# Power.net
KiCad netlist of a schematic drawn in Altium Designer
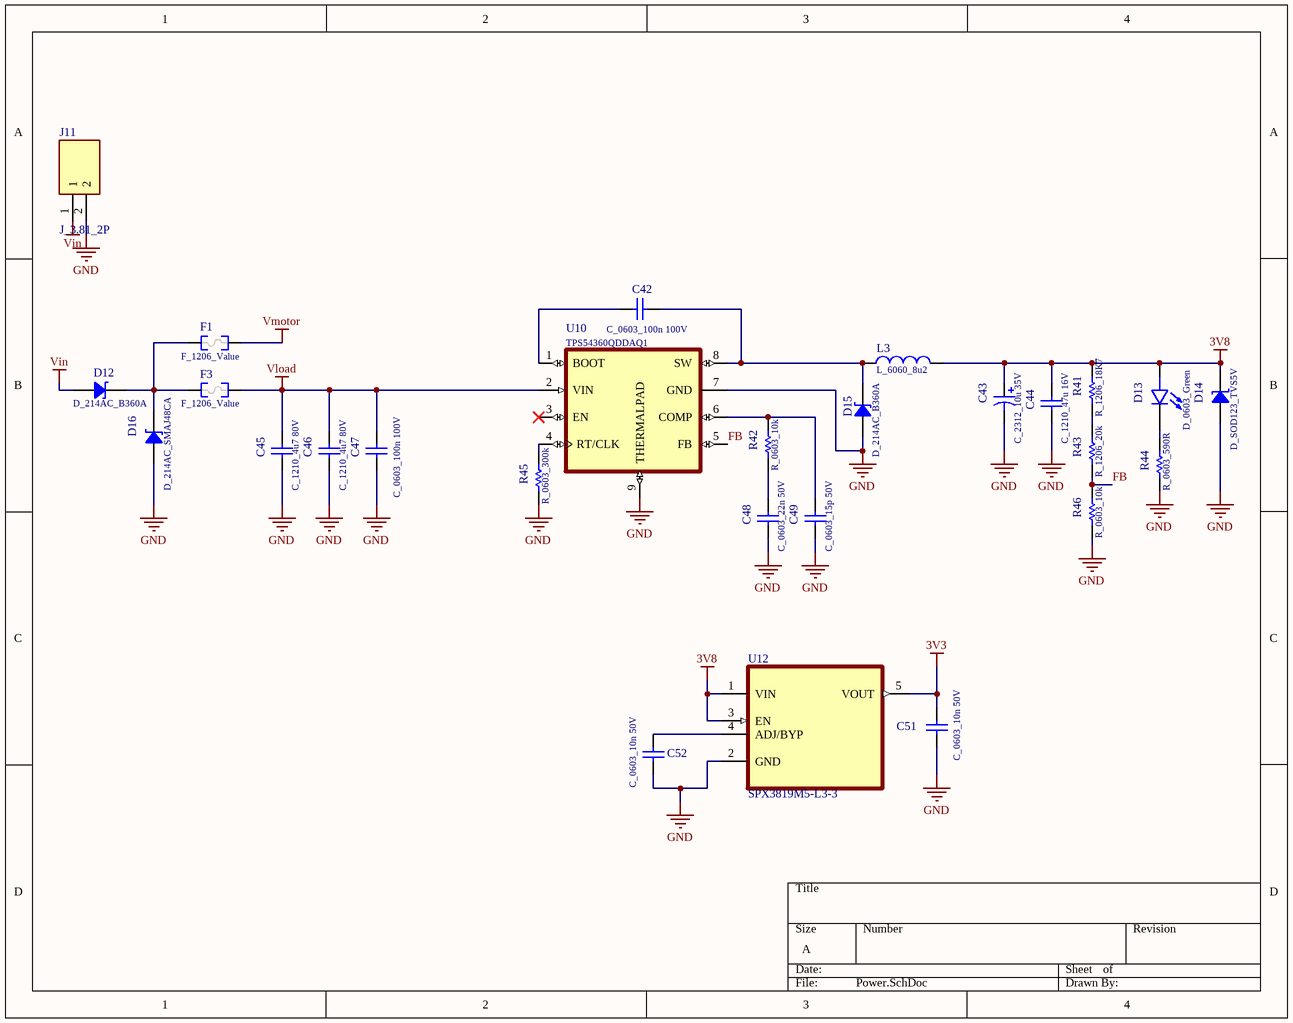
[diagram p0: Power.SchDoc]

(export (version "E")
  (design (tool "Eeschema 10.0.6"))
  (components
    (comp (ref "C42")
      (value "C_0603_100n 100V")
      (footprint "CAP 0603")
      (description "Capacitor")
      (fields (field (name "PUBLISHER") "Altium Limited"))
      (libsource (lib "HUE") (part "Cap"))
    )
    (comp (ref "C43")
      (value "C_2312_10u 35V")
      (footprint "CAP 2312 TAN")
      (description "Capacitor Tantalium")
      (fields (field (name "PUBLISHER") "Altium Limited"))
      (libsource (lib "HUE") (part "Cap Tantalium"))
    )
    (comp (ref "C44")
      (value "C_1210_47u 16V")
      (footprint "CAP 1210")
      (description "Capacitor")
      (fields (field (name "PUBLISHER") "Altium Limited"))
      (libsource (lib "HUE") (part "Cap"))
    )
    (comp (ref "C45")
      (value "C_1210_4u7 80V")
      (footprint "CAP 1210")
      (description "Capacitor")
      (fields (field (name "PUBLISHER") "Altium Limited"))
      (libsource (lib "HUE") (part "Cap"))
    )
    (comp (ref "C46")
      (value "C_1210_4u7 80V")
      (footprint "CAP 1210")
      (description "Capacitor")
      (fields (field (name "PUBLISHER") "Altium Limited"))
      (libsource (lib "HUE") (part "Cap"))
    )
    (comp (ref "C47")
      (value "C_0603_100n 100V")
      (footprint "CAP 0603")
      (description "Capacitor")
      (fields (field (name "PUBLISHER") "Altium Limited"))
      (libsource (lib "HUE") (part "Cap"))
    )
    (comp (ref "C48")
      (value "C_0603_22n 50V")
      (footprint "CAP 0603")
      (description "Capacitor")
      (fields (field (name "PUBLISHER") "Altium Limited"))
      (libsource (lib "HUE") (part "Cap"))
    )
    (comp (ref "C49")
      (value "C_0603_15p 50V")
      (footprint "CAP 0603")
      (description "Capacitor")
      (fields (field (name "PUBLISHER") "Altium Limited"))
      (libsource (lib "HUE") (part "Cap"))
    )
    (comp (ref "C51")
      (value "C_0603_10n 50V")
      (footprint "CAP 0603")
      (description "Capacitor")
      (fields (field (name "PUBLISHER") "Altium Limited"))
      (libsource (lib "HUE") (part "Cap"))
    )
    (comp (ref "C52")
      (value "C_0603_10n 50V")
      (footprint "CAP 0603")
      (description "Capacitor")
      (fields (field (name "PUBLISHER") "Altium Limited"))
      (libsource (lib "HUE") (part "Cap"))
    )
    (comp (ref "D12")
      (value "D_214AC_B360A")
      (footprint "DO214AC SMA")
      (description "Zener Diode")
      (libsource (lib "HUE") (part "Diode Zener"))
    )
    (comp (ref "D13")
      (value "D_0603_Green")
      (footprint "Led 0603")
      (description "Led")
      (fields (field (name "MP") "SML-D12FWT86") (field (name "MF") "Rohm"))
      (libsource (lib "HUE") (part "Led"))
    )
    (comp (ref "D14")
      (value "D_SOD123_TVS5V")
      (footprint "SOD-123")
      (description "Rectifier Diode")
      (libsource (lib "HUE") (part "DIODE TVS UNI"))
    )
    (comp (ref "D15")
      (value "D_214AC_B360A")
      (footprint "DO214AC SMA")
      (description "Zener Diode")
      (libsource (lib "HUE") (part "Diode Zener"))
    )
    (comp (ref "D16")
      (value "D_214AC_SMAJ48CA")
      (footprint "DO214AC SMA")
      (description "Zener Diode")
      (libsource (lib "HUE") (part "Diode Zener"))
    )
    (comp (ref "F1")
      (value "F_1206_Value")
      (footprint "FUSE 1206_3216 0.6MM")
      (libsource (lib "HUE") (part "Fuse"))
    )
    (comp (ref "F3")
      (value "F_1206_Value")
      (footprint "FUSE 1206_3216 0.6MM")
      (libsource (lib "HUE") (part "Fuse"))
    )
    (comp (ref "J11")
      (value "J_3.81_2P")
      (footprint "2 Pin PCB TB 3.81")
      (fields (field (name "MF") "CUI Devices") (field (name "MP") "TBP02R1-381-02BE"))
      (libsource (lib "HUE") (part "2 Pin PCB Terminal Block"))
    )
    (comp (ref "L3")
      (value "L_6060_8u2")
      (footprint "Inductor 6060")
      (description "Inductor")
      (fields (field (name "PUBLISHER") "Altium Limited"))
      (libsource (lib "HUE") (part "Inductor"))
    )
    (comp (ref "R41")
      (value "R_1206_18K7")
      (footprint "RES 1206")
      (description "Resistor")
      (fields (field (name "PUBLISHER") "Altium Limited"))
      (libsource (lib "HUE") (part "Res"))
    )
    (comp (ref "R42")
      (value "R_0603_10k")
      (footprint "RES 0603")
      (description "Resistor")
      (fields (field (name "PUBLISHER") "Altium Limited"))
      (libsource (lib "HUE") (part "Res"))
    )
    (comp (ref "R43")
      (value "R_1206_20k")
      (footprint "RES 1206")
      (description "Resistor")
      (fields (field (name "PUBLISHER") "Altium Limited"))
      (libsource (lib "HUE") (part "Res"))
    )
    (comp (ref "R44")
      (value "R_0603_590R")
      (footprint "RES 0603")
      (description "Resistor")
      (fields (field (name "PUBLISHER") "Altium Limited"))
      (libsource (lib "HUE") (part "Res"))
    )
    (comp (ref "R45")
      (value "R_0603_300k")
      (footprint "RES 0603")
      (description "Resistor")
      (fields (field (name "PUBLISHER") "Altium Limited"))
      (libsource (lib "HUE") (part "Res"))
    )
    (comp (ref "R46")
      (value "R_0603_10k")
      (footprint "RES 1206")
      (description "Resistor")
      (fields (field (name "PUBLISHER") "Altium Limited"))
      (libsource (lib "HUE") (part "Res"))
    )
    (comp (ref "U10")
      (value "TPS54360QDDAQ1")
      (footprint "SOIC8")
      (libsource (lib "HUE") (part "TPS54360QDDAQ1"))
    )
    (comp (ref "U12")
      (value "SPX3819M5-L3-3")
      (footprint "SOT23-5")
      (description "Linear Voltage Regulator IC 1 Output 500mA SOT-23-5")
      (fields (field (name "MP") "SPX3819M5-L/TR") (field (name "DIGI-KEY_PART_NUMBER") "1016-1871-1-ND"))
      (libsource (lib "HUE") (part "SPX3819M5-L"))
    )
  )
  (nets
    (net (code "1") (name "/FB") (class "Default")
      (node (ref "R43") (pin "1") (pinfunction "1_1") (pintype "passive"))
      (node (ref "R46") (pin "2") (pinfunction "2_2") (pintype "passive"))
      (node (ref "U10") (pin "5") (pinfunction "FB_5") (pintype "bidirectional"))
    )
    (net (code "2") (name "3V3") (class "Default")
      (node (ref "C51") (pin "2") (pinfunction "2_2") (pintype "passive"))
      (node (ref "U12") (pin "5") (pinfunction "VOUT_5") (pintype "output"))
    )
    (net (code "3") (name "3V8") (class "Default")
      (node (ref "C43") (pin "1") (pinfunction "1_1") (pintype "passive"))
      (node (ref "C44") (pin "1") (pinfunction "1_1") (pintype "passive"))
      (node (ref "D13") (pin "1") (pinfunction "A_1") (pintype "passive"))
      (node (ref "D14") (pin "2") (pinfunction "2_2") (pintype "passive"))
      (node (ref "L3") (pin "2") (pinfunction "2_2") (pintype "passive"))
      (node (ref "R41") (pin "2") (pinfunction "2_2") (pintype "passive"))
      (node (ref "U12") (pin "1") (pinfunction "VIN_1") (pintype "power_in"))
      (node (ref "U12") (pin "3") (pinfunction "EN_3") (pintype "input"))
    )
    (net (code "4") (name "GND") (class "Default")
      (node (ref "C43") (pin "2") (pinfunction "2_2") (pintype "passive"))
      (node (ref "C44") (pin "2") (pinfunction "2_2") (pintype "passive"))
      (node (ref "C45") (pin "2") (pinfunction "2_2") (pintype "passive"))
      (node (ref "C46") (pin "2") (pinfunction "2_2") (pintype "passive"))
      (node (ref "C47") (pin "2") (pinfunction "2_2") (pintype "passive"))
      (node (ref "C48") (pin "2") (pinfunction "2_2") (pintype "passive"))
      (node (ref "C49") (pin "2") (pinfunction "2_2") (pintype "passive"))
      (node (ref "C51") (pin "1") (pinfunction "1_1") (pintype "passive"))
      (node (ref "C52") (pin "1") (pinfunction "1_1") (pintype "passive"))
      (node (ref "D14") (pin "1") (pinfunction "1_1") (pintype "passive"))
      (node (ref "D15") (pin "1") (pinfunction "1_1") (pintype "passive"))
      (node (ref "D16") (pin "1") (pinfunction "1_1") (pintype "passive"))
      (node (ref "J11") (pin "2") (pinfunction "2_2") (pintype "passive"))
      (node (ref "R44") (pin "1") (pinfunction "1_1") (pintype "passive"))
      (node (ref "R45") (pin "1") (pinfunction "1_1") (pintype "passive"))
      (node (ref "R46") (pin "1") (pinfunction "1_1") (pintype "passive"))
      (node (ref "U10") (pin "7") (pinfunction "GND_7") (pintype "power_in"))
      (node (ref "U10") (pin "9") (pinfunction "THERMALPAD_9") (pintype "bidirectional"))
      (node (ref "U12") (pin "2") (pinfunction "GND_2") (pintype "passive"))
    )
    (net (code "5") (name "Net-(C48-Pad1)") (class "Default")
      (node (ref "C48") (pin "1") (pinfunction "1_1") (pintype "passive"))
      (node (ref "R42") (pin "1") (pinfunction "1_1") (pintype "passive"))
    )
    (net (code "6") (name "Net-(D12-Pad2)") (class "Default")
      (node (ref "D12") (pin "2") (pinfunction "2_2") (pintype "passive"))
      (node (ref "D16") (pin "2") (pinfunction "2_2") (pintype "passive"))
      (node (ref "F1") (pin "1") (pinfunction "1_1") (pintype "passive"))
      (node (ref "F3") (pin "1") (pinfunction "1_1") (pintype "passive"))
    )
    (net (code "7") (name "Net-(D13-C)") (class "Default")
      (node (ref "D13") (pin "2") (pinfunction "C_2") (pintype "passive"))
      (node (ref "R44") (pin "2") (pinfunction "2_2") (pintype "passive"))
    )
    (net (code "8") (name "Net-(R41-Pad1)") (class "Default")
      (node (ref "R41") (pin "1") (pinfunction "1_1") (pintype "passive"))
      (node (ref "R43") (pin "2") (pinfunction "2_2") (pintype "passive"))
    )
    (net (code "9") (name "Net-(U10-BOOT)") (class "Default")
      (node (ref "C42") (pin "2") (pinfunction "2_2") (pintype "passive"))
      (node (ref "U10") (pin "1") (pinfunction "BOOT_1") (pintype "bidirectional"))
    )
    (net (code "10") (name "Net-(U10-COMP)") (class "Default")
      (node (ref "C49") (pin "1") (pinfunction "1_1") (pintype "passive"))
      (node (ref "R42") (pin "2") (pinfunction "2_2") (pintype "passive"))
      (node (ref "U10") (pin "6") (pinfunction "COMP_6") (pintype "bidirectional"))
    )
    (net (code "11") (name "Net-(U10-RT{slash}CLK)") (class "Default")
      (node (ref "R45") (pin "2") (pinfunction "2_2") (pintype "passive"))
      (node (ref "U10") (pin "4") (pinfunction "RT/CLK_4") (pintype "bidirectional"))
    )
    (net (code "12") (name "Net-(U10-SW)") (class "Default")
      (node (ref "C42") (pin "1") (pinfunction "1_1") (pintype "passive"))
      (node (ref "D15") (pin "2") (pinfunction "2_2") (pintype "passive"))
      (node (ref "L3") (pin "1") (pinfunction "1_1") (pintype "passive"))
      (node (ref "U10") (pin "8") (pinfunction "SW_8") (pintype "bidirectional"))
    )
    (net (code "13") (name "Net-(U12-ADJ{slash}BYP)") (class "Default")
      (node (ref "C52") (pin "2") (pinfunction "2_2") (pintype "passive"))
      (node (ref "U12") (pin "4") (pinfunction "ADJ/BYP_4") (pintype "passive"))
    )
    (net (code "14") (name "Vin") (class "Default")
      (node (ref "D12") (pin "1") (pinfunction "1_1") (pintype "passive"))
      (node (ref "J11") (pin "1") (pinfunction "1_1") (pintype "passive"))
    )
    (net (code "15") (name "Vload") (class "Default")
      (node (ref "C45") (pin "1") (pinfunction "1_1") (pintype "passive"))
      (node (ref "C46") (pin "1") (pinfunction "1_1") (pintype "passive"))
      (node (ref "C47") (pin "1") (pinfunction "1_1") (pintype "passive"))
      (node (ref "F3") (pin "2") (pinfunction "2_2") (pintype "passive"))
      (node (ref "U10") (pin "2") (pinfunction "VIN_2") (pintype "input"))
    )
    (net (code "16") (name "Vmotor") (class "Default")
      (node (ref "F1") (pin "2") (pinfunction "2_2") (pintype "passive"))
    )
    (net (code "17") (name "unconnected-(U10-EN-Pad3)") (class "Default")
      (node (ref "U10") (pin "3") (pinfunction "EN_3") (pintype "bidirectional+no_connect"))
    )
  )
)
